# schematic.net
KiCad netlist of a schematic drawn in Altium Designer
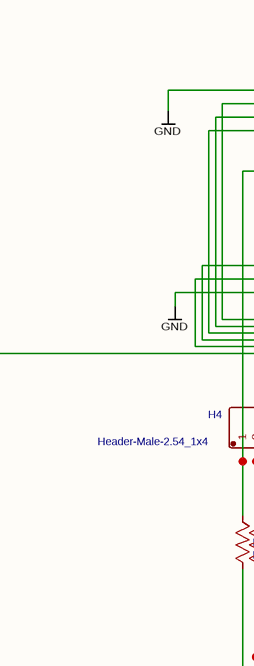
[diagram p0: schematic.schdoc, top left]
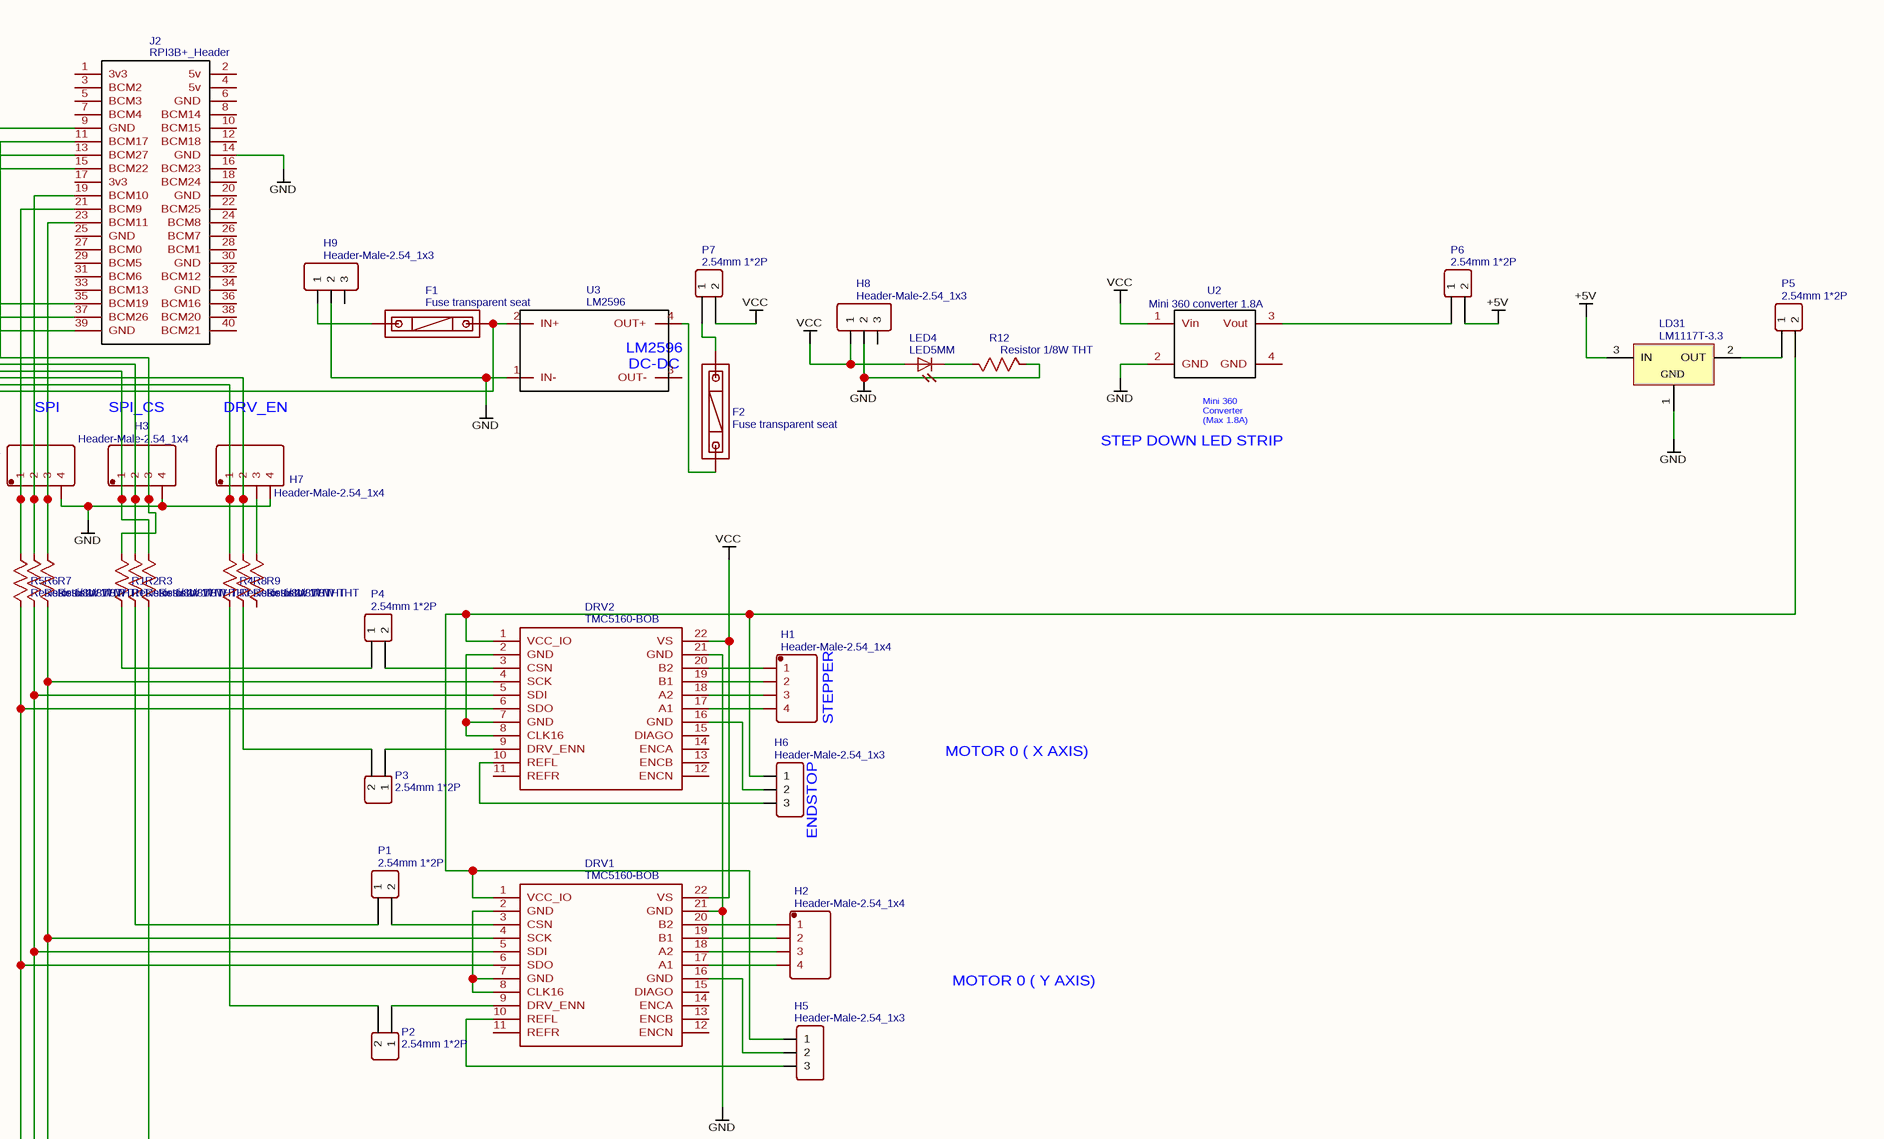
[diagram p1: schematic.schdoc, top right]
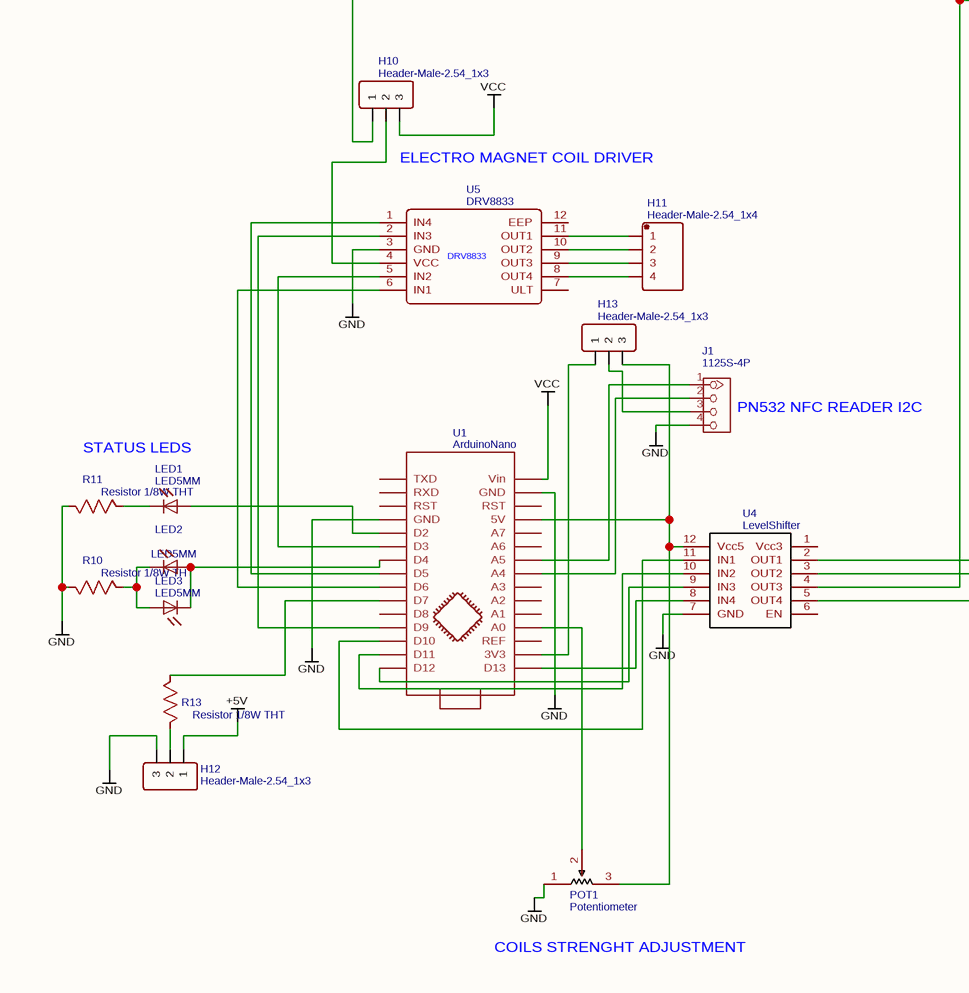
[diagram p2: schematic.schdoc, bottom left]

(export (version "E")
  (design (tool "Eeschema 10.0.6"))
  (components
    (comp (ref "DRV1")
      (value "TMC5160-BOB")
      (fields (field (name "CONTRIBUTOR") "alexackerman96"))
      (libsource (lib "altium-import") (part "root_0_TMC5160-BOB_"))
    )
    (comp (ref "DRV2")
      (value "TMC5160-BOB")
      (fields (field (name "CONTRIBUTOR") "alexackerman96"))
      (libsource (lib "altium-import") (part "root_0_TMC5160-BOB_"))
    )
    (comp (ref "F1")
      (value "Fuse transparent seat")
      (fields (field (name "BOM_SUPPLIER PART") "C58066"))
      (libsource (lib "altium-import") (part "root_0_Fuse transparent seat_"))
    )
    (comp (ref "F2")
      (value "Fuse transparent seat")
      (fields (field (name "BOM_SUPPLIER PART") "C58066"))
      (libsource (lib "altium-import") (part "root_1_Fuse transparent seat_"))
    )
    (comp (ref "H1")
      (value "Header-Male-2.54_1x4")
      (fields
        (field (name "BOM_MANUFACTURER PART") "210S-1*4P L=11.6MMGold-plated black")
        (field (name "BOM_SUPPLIER PART") "C124378")
        (field (name "CONTRIBUTOR") "LCSC")
      )
      (libsource (lib "altium-import") (part "root_0_Header-Male-2.54_1x4_"))
    )
    (comp (ref "H2")
      (value "Header-Male-2.54_1x4")
      (fields
        (field (name "BOM_MANUFACTURER PART") "210S-1*4P L=11.6MMGold-plated black")
        (field (name "BOM_SUPPLIER PART") "C124378")
        (field (name "CONTRIBUTOR") "LCSC")
      )
      (libsource (lib "altium-import") (part "root_0_Header-Male-2.54_1x4_"))
    )
    (comp (ref "H3")
      (value "Header-Male-2.54_1x4")
      (fields
        (field (name "BOM_MANUFACTURER PART") "210S-1*4P L=11.6MMGold-plated black")
        (field (name "BOM_SUPPLIER PART") "C124378")
        (field (name "CONTRIBUTOR") "LCSC")
      )
      (libsource (lib "altium-import") (part "root_1_Header-Male-2.54_1x4_"))
    )
    (comp (ref "H4")
      (value "Header-Male-2.54_1x4")
      (fields
        (field (name "BOM_MANUFACTURER PART") "210S-1*4P L=11.6MMGold-plated black")
        (field (name "BOM_SUPPLIER PART") "C124378")
        (field (name "CONTRIBUTOR") "LCSC")
      )
      (libsource (lib "altium-import") (part "root_1_Header-Male-2.54_1x4_"))
    )
    (comp (ref "H5")
      (value "Header-Male-2.54_1x3")
      (fields
        (field (name "BOM_MANUFACTURER PART") "Header2.54mm 1*3P")
        (field (name "BOM_SUPPLIER PART") "C49257")
      )
      (libsource (lib "altium-import") (part "root_0_Header-Male-2.54_1x3_"))
    )
    (comp (ref "H6")
      (value "Header-Male-2.54_1x3")
      (fields
        (field (name "BOM_MANUFACTURER PART") "Header2.54mm 1*3P")
        (field (name "BOM_SUPPLIER PART") "C49257")
      )
      (libsource (lib "altium-import") (part "root_0_Header-Male-2.54_1x3_"))
    )
    (comp (ref "H7")
      (value "Header-Male-2.54_1x4")
      (fields
        (field (name "BOM_MANUFACTURER PART") "210S-1*4P L=11.6MMGold-plated black")
        (field (name "BOM_SUPPLIER PART") "C124378")
        (field (name "CONTRIBUTOR") "LCSC")
      )
      (libsource (lib "altium-import") (part "root_1_Header-Male-2.54_1x4_"))
    )
    (comp (ref "H8")
      (value "Header-Male-2.54_1x3")
      (fields
        (field (name "BOM_MANUFACTURER PART") "Header2.54mm 1*3P")
        (field (name "BOM_SUPPLIER PART") "C49257")
      )
      (libsource (lib "altium-import") (part "root_1_Header-Male-2.54_1x3_"))
    )
    (comp (ref "H9")
      (value "Header-Male-2.54_1x3")
      (fields
        (field (name "BOM_MANUFACTURER PART") "Header2.54mm 1*3P")
        (field (name "BOM_SUPPLIER PART") "C49257")
      )
      (libsource (lib "altium-import") (part "root_1_Header-Male-2.54_1x3_"))
    )
    (comp (ref "H10")
      (value "Header-Male-2.54_1x3")
      (fields
        (field (name "BOM_MANUFACTURER PART") "Header2.54mm 1*3P")
        (field (name "BOM_SUPPLIER PART") "C49257")
      )
      (libsource (lib "altium-import") (part "root_1_Header-Male-2.54_1x3_"))
    )
    (comp (ref "H11")
      (value "Header-Male-2.54_1x4")
      (fields
        (field (name "BOM_MANUFACTURER PART") "210S-1*4P L=11.6MMGold-plated black")
        (field (name "BOM_SUPPLIER PART") "C124378")
        (field (name "CONTRIBUTOR") "LCSC")
      )
      (libsource (lib "altium-import") (part "root_0_Header-Male-2.54_1x4_"))
    )
    (comp (ref "H12")
      (value "Header-Male-2.54_1x3")
      (fields
        (field (name "BOM_MANUFACTURER PART") "Header2.54mm 1*3P")
        (field (name "BOM_SUPPLIER PART") "C49257")
      )
      (libsource (lib "altium-import") (part "root_3_Header-Male-2.54_1x3_"))
    )
    (comp (ref "H13")
      (value "Header-Male-2.54_1x3")
      (fields
        (field (name "BOM_MANUFACTURER PART") "Header2.54mm 1*3P")
        (field (name "BOM_SUPPLIER PART") "C49257")
      )
      (libsource (lib "altium-import") (part "root_1_Header-Male-2.54_1x3_"))
    )
    (comp (ref "J1")
      (value "1125S-4P")
      (description "DIP Grove")
      (libsource (lib "altium-import") (part "root_0_1125S-4P_"))
    )
    (comp (ref "J2")
      (value "RPI3B+_Header")
      (fields
        (field (name "BOM_MANUFACTURER PART") "61304021121")
        (field (name "BOM_SUPPLIER PART") "732-5310-ND")
        (field (name "CONTRIBUTOR") "boulou")
      )
      (libsource (lib "altium-import") (part "root_0_RPI3B+_Header_"))
    )
    (comp (ref "LD31")
      (value "LM1117T-3.3")
      (fields (field (name "CONTRIBUTOR") "M474"))
      (libsource (lib "altium-import") (part "root_0_LM1117T-3.3_"))
    )
    (comp (ref "LED1")
      (value "LED5MM")
      (description "LEDs")
      (fields (field (name "CONTRIBUTOR") "Pinoccio"))
      (libsource (lib "altium-import") (part "root_3_LED5MM_"))
    )
    (comp (ref "LED2")
      (value "LED5MM")
      (description "LEDs")
      (fields (field (name "CONTRIBUTOR") "Pinoccio"))
      (libsource (lib "altium-import") (part "root_3_LED5MM_"))
    )
    (comp (ref "LED3")
      (value "LED5MM")
      (description "LEDs")
      (fields (field (name "CONTRIBUTOR") "Pinoccio"))
      (libsource (lib "altium-import") (part "root_1_LED5MM_"))
    )
    (comp (ref "LED4")
      (value "LED5MM")
      (description "LEDs")
      (fields (field (name "CONTRIBUTOR") "Pinoccio"))
      (libsource (lib "altium-import") (part "root_1_LED5MM_"))
    )
    (comp (ref "P1")
      (value "2.54mm 1*2P")
      (fields (field (name "BOM_SUPPLIER PART") "C36717"))
      (libsource (lib "altium-import") (part "root_1_2.54mm 1*2P_"))
    )
    (comp (ref "P2")
      (value "2.54mm 1*2P")
      (fields (field (name "BOM_SUPPLIER PART") "C36717"))
      (libsource (lib "altium-import") (part "root_3_2.54mm 1*2P_"))
    )
    (comp (ref "P3")
      (value "2.54mm 1*2P")
      (fields (field (name "BOM_SUPPLIER PART") "C36717"))
      (libsource (lib "altium-import") (part "root_3_2.54mm 1*2P_"))
    )
    (comp (ref "P4")
      (value "2.54mm 1*2P")
      (fields (field (name "BOM_SUPPLIER PART") "C36717"))
      (libsource (lib "altium-import") (part "root_1_2.54mm 1*2P_"))
    )
    (comp (ref "P5")
      (value "2.54mm 1*2P")
      (fields (field (name "BOM_SUPPLIER PART") "C36717"))
      (libsource (lib "altium-import") (part "root_1_2.54mm 1*2P_"))
    )
    (comp (ref "P6")
      (value "2.54mm 1*2P")
      (fields (field (name "BOM_SUPPLIER PART") "C36717"))
      (libsource (lib "altium-import") (part "root_1_2.54mm 1*2P_"))
    )
    (comp (ref "P7")
      (value "2.54mm 1*2P")
      (fields (field (name "BOM_SUPPLIER PART") "C36717"))
      (libsource (lib "altium-import") (part "root_1_2.54mm 1*2P_"))
    )
    (comp (ref "POT1")
      (value "Potentiometer")
      (fields
        (field (name "BOM_MANUFACTURER PART") "potentiometer")
        (field (name "CONTRIBUTOR") "Tommaso Mariotti")
      )
      (libsource (lib "altium-import") (part "root_0_Potentiometer_"))
    )
    (comp (ref "R1")
      (value "Resistor 1/8W THT")
      (fields (field (name "BOM_MANUFACTURER PART") "Generic") (field (name "CONTRIBUTOR") "tyvogelpohl"))
      (libsource (lib "altium-import") (part "root_1_Resistor 1/8W THT_"))
    )
    (comp (ref "R2")
      (value "Resistor 1/8W THT")
      (fields (field (name "BOM_MANUFACTURER PART") "Generic") (field (name "CONTRIBUTOR") "tyvogelpohl"))
      (libsource (lib "altium-import") (part "root_1_Resistor 1/8W THT_"))
    )
    (comp (ref "R3")
      (value "Resistor 1/8W THT")
      (fields (field (name "BOM_MANUFACTURER PART") "Generic") (field (name "CONTRIBUTOR") "tyvogelpohl"))
      (libsource (lib "altium-import") (part "root_1_Resistor 1/8W THT_"))
    )
    (comp (ref "R4")
      (value "Resistor 1/8W THT")
      (fields (field (name "BOM_MANUFACTURER PART") "Generic") (field (name "CONTRIBUTOR") "tyvogelpohl"))
      (libsource (lib "altium-import") (part "root_1_Resistor 1/8W THT_"))
    )
    (comp (ref "R5")
      (value "Resistor 1/8W THT")
      (fields (field (name "BOM_MANUFACTURER PART") "Generic") (field (name "CONTRIBUTOR") "tyvogelpohl"))
      (libsource (lib "altium-import") (part "root_1_Resistor 1/8W THT_"))
    )
    (comp (ref "R6")
      (value "Resistor 1/8W THT")
      (fields (field (name "BOM_MANUFACTURER PART") "Generic") (field (name "CONTRIBUTOR") "tyvogelpohl"))
      (libsource (lib "altium-import") (part "root_1_Resistor 1/8W THT_"))
    )
    (comp (ref "R7")
      (value "Resistor 1/8W THT")
      (fields (field (name "BOM_MANUFACTURER PART") "Generic") (field (name "CONTRIBUTOR") "tyvogelpohl"))
      (libsource (lib "altium-import") (part "root_1_Resistor 1/8W THT_"))
    )
    (comp (ref "R8")
      (value "Resistor 1/8W THT")
      (fields (field (name "BOM_MANUFACTURER PART") "Generic") (field (name "CONTRIBUTOR") "tyvogelpohl"))
      (libsource (lib "altium-import") (part "root_1_Resistor 1/8W THT_"))
    )
    (comp (ref "R9")
      (value "Resistor 1/8W THT")
      (fields (field (name "BOM_MANUFACTURER PART") "Generic") (field (name "CONTRIBUTOR") "tyvogelpohl"))
      (libsource (lib "altium-import") (part "root_1_Resistor 1/8W THT_"))
    )
    (comp (ref "R10")
      (value "Resistor 1/8W THT")
      (fields (field (name "BOM_MANUFACTURER PART") "Generic") (field (name "CONTRIBUTOR") "tyvogelpohl"))
      (libsource (lib "altium-import") (part "root_2_Resistor 1/8W THT_"))
    )
    (comp (ref "R11")
      (value "Resistor 1/8W THT")
      (fields (field (name "BOM_MANUFACTURER PART") "Generic") (field (name "CONTRIBUTOR") "tyvogelpohl"))
      (libsource (lib "altium-import") (part "root_2_Resistor 1/8W THT_"))
    )
    (comp (ref "R12")
      (value "Resistor 1/8W THT")
      (fields (field (name "BOM_MANUFACTURER PART") "Generic") (field (name "CONTRIBUTOR") "tyvogelpohl"))
      (libsource (lib "altium-import") (part "root_0_Resistor 1/8W THT_"))
    )
    (comp (ref "R13")
      (value "Resistor 1/8W THT")
      (fields (field (name "BOM_MANUFACTURER PART") "Generic") (field (name "CONTRIBUTOR") "tyvogelpohl"))
      (libsource (lib "altium-import") (part "root_3_Resistor 1/8W THT_"))
    )
    (comp (ref "U1")
      (value "ArduinoNano")
      (fields (field (name "CONTRIBUTOR") "vincint810923"))
      (libsource (lib "altium-import") (part "root_0_ArduinoNano_"))
    )
    (comp (ref "U2")
      (value "Mini 360 converter 1.8A")
      (fields
        (field (name "BOM_MANUFACTURER PART") "Mini 360 step down converter 1.8A")
        (field (name "CONTRIBUTOR") "Hankwon Chang (InterStellarCloud)")
      )
      (libsource (lib "altium-import") (part "root_0_Mini 360 converter 1.8A_"))
    )
    (comp (ref "U3")
      (value "LM2596")
      (fields (field (name "CONTRIBUTOR") "Azriel Hutagalung"))
      (libsource (lib "altium-import") (part "root_0_LM2596_"))
    )
    (comp (ref "U4")
      (value "LevelShifter")
      (fields (field (name "CONTRIBUTOR") "max.helmrich"))
      (libsource (lib "altium-import") (part "root_0_LevelShifter_"))
    )
    (comp (ref "U5") (value "DRV8833") (libsource (lib "altium-import") (part "root_0_DRV8833_")))
  )
  (nets
    (net (code "1") (name "+5V") (class "Default")
      (node (ref "H12") (pin "1") (pinfunction "1_1") (pintype "passive"))
      (node (ref "LD31") (pin "3") (pinfunction "IN_3") (pintype "passive"))
      (node (ref "P6") (pin "2") (pinfunction "2_2") (pintype "passive"))
    )
    (net (code "2") (name "GND") (class "Default")
      (node (ref "DRV1") (pin "21") (pinfunction "GND_21") (pintype "passive"))
      (node (ref "DRV2") (pin "21") (pinfunction "GND_21") (pintype "passive"))
      (node (ref "H12") (pin "3") (pinfunction "3_3") (pintype "passive"))
      (node (ref "H3") (pin "4") (pinfunction "4_4") (pintype "passive"))
      (node (ref "H4") (pin "4") (pinfunction "4_4") (pintype "passive"))
      (node (ref "H7") (pin "4") (pinfunction "4_4") (pintype "passive"))
      (node (ref "H8") (pin "2") (pinfunction "2_2") (pintype "passive"))
      (node (ref "H9") (pin "2") (pinfunction "2_2") (pintype "passive"))
      (node (ref "J1") (pin "4") (pinfunction "4_4") (pintype "passive"))
      (node (ref "J2") (pin "14") (pinfunction "GND_14") (pintype "passive"))
      (node (ref "J2") (pin "39") (pinfunction "GND_39") (pintype "passive"))
      (node (ref "J2") (pin "9") (pinfunction "GND_9") (pintype "passive"))
      (node (ref "LD31") (pin "1") (pinfunction "GND_1") (pintype "passive"))
      (node (ref "POT1") (pin "1") (pinfunction "1_1") (pintype "passive"))
      (node (ref "R10") (pin "2") (pinfunction "2_2") (pintype "passive"))
      (node (ref "R11") (pin "2") (pinfunction "2_2") (pintype "passive"))
      (node (ref "R12") (pin "2") (pinfunction "2_2") (pintype "passive"))
      (node (ref "U1") (pin "29") (pinfunction "GND_29") (pintype "passive"))
      (node (ref "U1") (pin "4") (pinfunction "GND_4") (pintype "passive"))
      (node (ref "U2") (pin "2") (pinfunction "GND_2") (pintype "passive"))
      (node (ref "U3") (pin "1") (pinfunction "IN-_1") (pintype "passive"))
      (node (ref "U4") (pin "7") (pinfunction "GND_7") (pintype "passive"))
      (node (ref "U5") (pin "3") (pinfunction "GND_3") (pintype "passive"))
    )
    (net (code "3") (name "Net-(DRV1-A1)") (class "Default")
      (node (ref "DRV1") (pin "17") (pinfunction "A1_17") (pintype "passive"))
      (node (ref "H2") (pin "4") (pinfunction "4_4") (pintype "passive"))
    )
    (net (code "4") (name "Net-(DRV1-A2)") (class "Default")
      (node (ref "DRV1") (pin "18") (pinfunction "A2_18") (pintype "passive"))
      (node (ref "H2") (pin "3") (pinfunction "3_3") (pintype "passive"))
    )
    (net (code "5") (name "Net-(DRV1-B1)") (class "Default")
      (node (ref "DRV1") (pin "19") (pinfunction "B1_19") (pintype "passive"))
      (node (ref "H2") (pin "2") (pinfunction "2_2") (pintype "passive"))
    )
    (net (code "6") (name "Net-(DRV1-B2)") (class "Default")
      (node (ref "DRV1") (pin "20") (pinfunction "B2_20") (pintype "passive"))
      (node (ref "H2") (pin "1") (pinfunction "1_1") (pintype "passive"))
    )
    (net (code "7") (name "Net-(DRV1-CLK16)") (class "Default")
      (node (ref "DRV1") (pin "2") (pinfunction "GND_2") (pintype "passive"))
      (node (ref "DRV1") (pin "7") (pinfunction "GND_7") (pintype "passive"))
      (node (ref "DRV1") (pin "8") (pinfunction "CLK16_8") (pintype "passive"))
    )
    (net (code "8") (name "Net-(DRV1-CSN)") (class "Default")
      (node (ref "DRV1") (pin "3") (pinfunction "CSN_3") (pintype "passive"))
      (node (ref "P1") (pin "2") (pinfunction "2_2") (pintype "passive"))
    )
    (net (code "9") (name "Net-(DRV1-DRV_ENN)") (class "Default")
      (node (ref "DRV1") (pin "9") (pinfunction "DRV_ENN_9") (pintype "passive"))
      (node (ref "P2") (pin "1") (pinfunction "1_1") (pintype "passive"))
    )
    (net (code "10") (name "Net-(DRV1-GND-Pad16)") (class "Default")
      (node (ref "DRV1") (pin "16") (pinfunction "GND_16") (pintype "passive"))
      (node (ref "H5") (pin "2") (pinfunction "2_2") (pintype "passive"))
    )
    (net (code "11") (name "Net-(DRV1-REFL)") (class "Default")
      (node (ref "DRV1") (pin "10") (pinfunction "REFL_10") (pintype "passive"))
      (node (ref "H5") (pin "3") (pinfunction "3_3") (pintype "passive"))
    )
    (net (code "12") (name "Net-(DRV1-SCK)") (class "Default")
      (node (ref "DRV1") (pin "4") (pinfunction "SCK_4") (pintype "passive"))
      (node (ref "DRV2") (pin "4") (pinfunction "SCK_4") (pintype "passive"))
      (node (ref "R7") (pin "1") (pinfunction "1_1") (pintype "passive"))
      (node (ref "U4") (pin "5") (pinfunction "OUT4_5") (pintype "passive"))
    )
    (net (code "13") (name "Net-(DRV1-SDI)") (class "Default")
      (node (ref "DRV1") (pin "5") (pinfunction "SDI_5") (pintype "passive"))
      (node (ref "DRV2") (pin "5") (pinfunction "SDI_5") (pintype "passive"))
      (node (ref "R6") (pin "1") (pinfunction "1_1") (pintype "passive"))
      (node (ref "U4") (pin "3") (pinfunction "OUT2_3") (pintype "passive"))
    )
    (net (code "14") (name "Net-(DRV1-SDO)") (class "Default")
      (node (ref "DRV1") (pin "6") (pinfunction "SDO_6") (pintype "passive"))
      (node (ref "DRV2") (pin "6") (pinfunction "SDO_6") (pintype "passive"))
      (node (ref "R5") (pin "1") (pinfunction "1_1") (pintype "passive"))
      (node (ref "U4") (pin "4") (pinfunction "OUT3_4") (pintype "passive"))
    )
    (net (code "15") (name "Net-(DRV1-VCC_IO)") (class "Default")
      (node (ref "DRV1") (pin "1") (pinfunction "VCC_IO_1") (pintype "passive"))
      (node (ref "DRV2") (pin "1") (pinfunction "VCC_IO_1") (pintype "passive"))
      (node (ref "H5") (pin "1") (pinfunction "1_1") (pintype "passive"))
      (node (ref "H6") (pin "1") (pinfunction "1_1") (pintype "passive"))
      (node (ref "P5") (pin "2") (pinfunction "2_2") (pintype "passive"))
    )
    (net (code "16") (name "Net-(DRV2-A1)") (class "Default")
      (node (ref "DRV2") (pin "17") (pinfunction "A1_17") (pintype "passive"))
      (node (ref "H1") (pin "4") (pinfunction "4_4") (pintype "passive"))
    )
    (net (code "17") (name "Net-(DRV2-A2)") (class "Default")
      (node (ref "DRV2") (pin "18") (pinfunction "A2_18") (pintype "passive"))
      (node (ref "H1") (pin "3") (pinfunction "3_3") (pintype "passive"))
    )
    (net (code "18") (name "Net-(DRV2-B1)") (class "Default")
      (node (ref "DRV2") (pin "19") (pinfunction "B1_19") (pintype "passive"))
      (node (ref "H1") (pin "2") (pinfunction "2_2") (pintype "passive"))
    )
    (net (code "19") (name "Net-(DRV2-B2)") (class "Default")
      (node (ref "DRV2") (pin "20") (pinfunction "B2_20") (pintype "passive"))
      (node (ref "H1") (pin "1") (pinfunction "1_1") (pintype "passive"))
    )
    (net (code "20") (name "Net-(DRV2-CLK16)") (class "Default")
      (node (ref "DRV2") (pin "2") (pinfunction "GND_2") (pintype "passive"))
      (node (ref "DRV2") (pin "7") (pinfunction "GND_7") (pintype "passive"))
      (node (ref "DRV2") (pin "8") (pinfunction "CLK16_8") (pintype "passive"))
    )
    (net (code "21") (name "Net-(DRV2-CSN)") (class "Default")
      (node (ref "DRV2") (pin "3") (pinfunction "CSN_3") (pintype "passive"))
      (node (ref "P4") (pin "2") (pinfunction "2_2") (pintype "passive"))
    )
    (net (code "22") (name "Net-(DRV2-DRV_ENN)") (class "Default")
      (node (ref "DRV2") (pin "9") (pinfunction "DRV_ENN_9") (pintype "passive"))
      (node (ref "P3") (pin "1") (pinfunction "1_1") (pintype "passive"))
    )
    (net (code "23") (name "Net-(DRV2-GND-Pad16)") (class "Default")
      (node (ref "DRV2") (pin "16") (pinfunction "GND_16") (pintype "passive"))
      (node (ref "H6") (pin "2") (pinfunction "2_2") (pintype "passive"))
    )
    (net (code "24") (name "Net-(DRV2-REFL)") (class "Default")
      (node (ref "DRV2") (pin "10") (pinfunction "REFL_10") (pintype "passive"))
      (node (ref "H6") (pin "3") (pinfunction "3_3") (pintype "passive"))
    )
    (net (code "25") (name "Net-(F1-Pad1)") (class "Default")
      (node (ref "F1") (pin "1") (pinfunction "1_1") (pintype "passive"))
      (node (ref "H9") (pin "1") (pinfunction "1_1") (pintype "passive"))
    )
    (net (code "26") (name "Net-(F2-Pad2)") (class "Default")
      (node (ref "F2") (pin "2") (pinfunction "2_2") (pintype "passive"))
      (node (ref "P7") (pin "1") (pinfunction "1_1") (pintype "passive"))
    )
    (net (code "27") (name "Net-(H7-Pad3)") (class "Default")
      (node (ref "H7") (pin "3") (pinfunction "3_3") (pintype "passive"))
      (node (ref "R9") (pin "2") (pinfunction "2_2") (pintype "passive"))
    )
    (net (code "28") (name "Net-(H12-Pad2)") (class "Default")
      (node (ref "H12") (pin "2") (pinfunction "2_2") (pintype "passive"))
      (node (ref "R13") (pin "2") (pinfunction "2_2") (pintype "passive"))
    )
    (net (code "29") (name "Net-(H13-Pad2)") (class "Default")
      (node (ref "H13") (pin "2") (pinfunction "2_2") (pintype "passive"))
      (node (ref "J1") (pin "3") (pinfunction "3_3") (pintype "passive"))
    )
    (net (code "30") (name "Net-(J2-BCM9)") (class "Default")
      (node (ref "H4") (pin "1") (pinfunction "1_1") (pintype "passive"))
      (node (ref "J2") (pin "21") (pinfunction "BCM9_21") (pintype "passive"))
      (node (ref "R5") (pin "2") (pinfunction "2_2") (pintype "passive"))
    )
    (net (code "31") (name "Net-(J2-BCM10)") (class "Default")
      (node (ref "H4") (pin "2") (pinfunction "2_2") (pintype "passive"))
      (node (ref "J2") (pin "19") (pinfunction "BCM10_19") (pintype "passive"))
      (node (ref "R6") (pin "2") (pinfunction "2_2") (pintype "passive"))
    )
    (net (code "32") (name "Net-(J2-BCM11)") (class "Default")
      (node (ref "H4") (pin "3") (pinfunction "3_3") (pintype "passive"))
      (node (ref "J2") (pin "23") (pinfunction "BCM11_23") (pintype "passive"))
      (node (ref "R7") (pin "2") (pinfunction "2_2") (pintype "passive"))
    )
    (net (code "33") (name "Net-(J2-BCM17)") (class "Default")
      (node (ref "H3") (pin "3") (pinfunction "3_3") (pintype "passive"))
      (node (ref "J2") (pin "11") (pinfunction "BCM17_11") (pintype "passive"))
      (node (ref "R1") (pin "2") (pinfunction "2_2") (pintype "passive"))
    )
    (net (code "34") (name "Net-(J2-BCM19)") (class "Default")
      (node (ref "H7") (pin "2") (pinfunction "2_2") (pintype "passive"))
      (node (ref "J2") (pin "35") (pinfunction "BCM19_35") (pintype "passive"))
      (node (ref "R8") (pin "2") (pinfunction "2_2") (pintype "passive"))
    )
    (net (code "35") (name "Net-(J2-BCM22)") (class "Default")
      (node (ref "H3") (pin "1") (pinfunction "1_1") (pintype "passive"))
      (node (ref "J2") (pin "15") (pinfunction "BCM22_15") (pintype "passive"))
      (node (ref "R3") (pin "2") (pinfunction "2_2") (pintype "passive"))
    )
    (net (code "36") (name "Net-(J2-BCM26)") (class "Default")
      (node (ref "H7") (pin "1") (pinfunction "1_1") (pintype "passive"))
      (node (ref "J2") (pin "37") (pinfunction "BCM26_37") (pintype "passive"))
      (node (ref "R4") (pin "2") (pinfunction "2_2") (pintype "passive"))
    )
    (net (code "37") (name "Net-(J2-BCM27)") (class "Default")
      (node (ref "H3") (pin "2") (pinfunction "2_2") (pintype "passive"))
      (node (ref "J2") (pin "13") (pinfunction "BCM27_13") (pintype "passive"))
      (node (ref "R2") (pin "2") (pinfunction "2_2") (pintype "passive"))
    )
    (net (code "38") (name "Net-(LD31-OUT)") (class "Default")
      (node (ref "LD31") (pin "2") (pinfunction "OUT_2") (pintype "passive"))
      (node (ref "P5") (pin "1") (pinfunction "1_1") (pintype "passive"))
    )
    (net (code "39") (name "Net-(LED1-C)") (class "Default")
      (node (ref "LED1") (pin "K") (pinfunction "C_K") (pintype "passive"))
      (node (ref "R11") (pin "1") (pinfunction "1_1") (pintype "passive"))
    )
    (net (code "40") (name "Net-(LED2-C)") (class "Default")
      (node (ref "LED2") (pin "K") (pinfunction "C_K") (pintype "passive"))
      (node (ref "LED3") (pin "A") (pinfunction "A_A") (pintype "passive"))
      (node (ref "R10") (pin "1") (pinfunction "1_1") (pintype "passive"))
    )
    (net (code "41") (name "Net-(LED3-C)") (class "Default")
      (node (ref "LED2") (pin "A") (pinfunction "A_A") (pintype "passive"))
      (node (ref "LED3") (pin "K") (pinfunction "C_K") (pintype "passive"))
      (node (ref "U1") (pin "7") (pinfunction "D4_7") (pintype "passive"))
    )
    (net (code "42") (name "Net-(LED4-C)") (class "Default")
      (node (ref "LED4") (pin "K") (pinfunction "C_K") (pintype "passive"))
      (node (ref "R12") (pin "1") (pinfunction "1_1") (pintype "passive"))
    )
    (net (code "43") (name "Net-(P1-Pad1)") (class "Default")
      (node (ref "P1") (pin "1") (pinfunction "1_1") (pintype "passive"))
      (node (ref "R2") (pin "1") (pinfunction "1_1") (pintype "passive"))
    )
    (net (code "44") (name "Net-(P2-Pad2)") (class "Default")
      (node (ref "P2") (pin "2") (pinfunction "2_2") (pintype "passive"))
      (node (ref "R4") (pin "1") (pinfunction "1_1") (pintype "passive"))
    )
    (net (code "45") (name "Net-(P3-Pad2)") (class "Default")
      (node (ref "P3") (pin "2") (pinfunction "2_2") (pintype "passive"))
      (node (ref "R8") (pin "1") (pinfunction "1_1") (pintype "passive"))
    )
    (net (code "46") (name "Net-(P4-Pad1)") (class "Default")
      (node (ref "P4") (pin "1") (pinfunction "1_1") (pintype "passive"))
      (node (ref "R1") (pin "1") (pinfunction "1_1") (pintype "passive"))
    )
    (net (code "47") (name "Net-(U1-3V3)") (class "Default")
      (node (ref "H13") (pin "1") (pinfunction "1_1") (pintype "passive"))
      (node (ref "U1") (pin "17") (pinfunction "3V3_17") (pintype "passive"))
    )
    (net (code "48") (name "Net-(U1-5V)") (class "Default")
      (node (ref "H13") (pin "3") (pinfunction "3_3") (pintype "passive"))
      (node (ref "POT1") (pin "3") (pinfunction "3_3") (pintype "passive"))
      (node (ref "U1") (pin "27") (pinfunction "5V_27") (pintype "passive"))
      (node (ref "U4") (pin "12") (pinfunction "Vcc5_12") (pintype "passive"))
    )
    (net (code "49") (name "Net-(U1-A0)") (class "Default")
      (node (ref "POT1") (pin "2") (pinfunction "2_2") (pintype "passive"))
      (node (ref "U1") (pin "19") (pinfunction "A0_19") (pintype "passive"))
    )
    (net (code "50") (name "Net-(U1-A4)") (class "Default")
      (node (ref "J1") (pin "2") (pinfunction "2_2") (pintype "passive"))
      (node (ref "U1") (pin "23") (pinfunction "A4_23") (pintype "passive"))
    )
    (net (code "51") (name "Net-(U1-A5)") (class "Default")
      (node (ref "J1") (pin "1") (pinfunction "1_1") (pintype "passive"))
      (node (ref "U1") (pin "24") (pinfunction "A5_24") (pintype "passive"))
    )
    (net (code "52") (name "Net-(U1-D2)") (class "Default")
      (node (ref "LED1") (pin "A") (pinfunction "A_A") (pintype "passive"))
      (node (ref "U1") (pin "5") (pinfunction "D2_5") (pintype "passive"))
    )
    (net (code "53") (name "Net-(U1-D3)") (class "Default")
      (node (ref "U1") (pin "6") (pinfunction "D3_6") (pintype "passive"))
      (node (ref "U5") (pin "5") (pinfunction "IN2_5") (pintype "passive"))
    )
    (net (code "54") (name "Net-(U1-D5)") (class "Default")
      (node (ref "U1") (pin "8") (pinfunction "D5_8") (pintype "passive"))
      (node (ref "U5") (pin "1") (pinfunction "IN4_1") (pintype "passive"))
    )
    (net (code "55") (name "Net-(U1-D6)") (class "Default")
      (node (ref "U1") (pin "9") (pinfunction "D6_9") (pintype "passive"))
      (node (ref "U5") (pin "6") (pinfunction "IN1_6") (pintype "passive"))
    )
    (net (code "56") (name "Net-(U1-D7)") (class "Default")
      (node (ref "R13") (pin "1") (pinfunction "1_1") (pintype "passive"))
      (node (ref "U1") (pin "10") (pinfunction "D7_10") (pintype "passive"))
    )
    (net (code "57") (name "Net-(U1-D9)") (class "Default")
      (node (ref "U1") (pin "12") (pinfunction "D9_12") (pintype "passive"))
      (node (ref "U5") (pin "2") (pinfunction "IN3_2") (pintype "passive"))
    )
    (net (code "58") (name "Net-(U1-D10)") (class "Default")
      (node (ref "U1") (pin "13") (pinfunction "D10_13") (pintype "passive"))
      (node (ref "U4") (pin "11") (pinfunction "IN1_11") (pintype "passive"))
    )
    (net (code "59") (name "Net-(U1-D11)") (class "Default")
      (node (ref "U1") (pin "14") (pinfunction "D11_14") (pintype "passive"))
      (node (ref "U4") (pin "10") (pinfunction "IN2_10") (pintype "passive"))
    )
    (net (code "60") (name "Net-(U1-D12)") (class "Default")
      (node (ref "U1") (pin "15") (pinfunction "D12_15") (pintype "passive"))
      (node (ref "U4") (pin "9") (pinfunction "IN3_9") (pintype "passive"))
    )
    (net (code "61") (name "Net-(U1-D13)") (class "Default")
      (node (ref "U1") (pin "16") (pinfunction "D13_16") (pintype "passive"))
      (node (ref "U4") (pin "8") (pinfunction "IN4_8") (pintype "passive"))
    )
    (net (code "62") (name "Net-(U2-Vout)") (class "Default")
      (node (ref "P6") (pin "1") (pinfunction "1_1") (pintype "passive"))
      (node (ref "U2") (pin "3") (pinfunction "Vout_3") (pintype "passive"))
    )
    (net (code "63") (name "Net-(U3-IN+)") (class "Default")
      (node (ref "F1") (pin "2") (pinfunction "2_2") (pintype "passive"))
      (node (ref "H10") (pin "1") (pinfunction "1_1") (pintype "passive"))
      (node (ref "U3") (pin "2") (pinfunction "IN+_2") (pintype "passive"))
    )
    (net (code "64") (name "Net-(U3-OUT+)") (class "Default")
      (node (ref "F2") (pin "1") (pinfunction "1_1") (pintype "passive"))
      (node (ref "U3") (pin "4") (pinfunction "OUT+_4") (pintype "passive"))
    )
    (net (code "65") (name "Net-(U4-OUT1)") (class "Default")
      (node (ref "R3") (pin "1") (pinfunction "1_1") (pintype "passive"))
      (node (ref "U4") (pin "2") (pinfunction "OUT1_2") (pintype "passive"))
    )
    (net (code "66") (name "Net-(U5-OUT1)") (class "Default")
      (node (ref "H11") (pin "1") (pinfunction "1_1") (pintype "passive"))
      (node (ref "U5") (pin "11") (pinfunction "OUT1_11") (pintype "passive"))
    )
    (net (code "67") (name "Net-(U5-OUT2)") (class "Default")
      (node (ref "H11") (pin "2") (pinfunction "2_2") (pintype "passive"))
      (node (ref "U5") (pin "10") (pinfunction "OUT2_10") (pintype "passive"))
    )
    (net (code "68") (name "Net-(U5-OUT3)") (class "Default")
      (node (ref "H11") (pin "3") (pinfunction "3_3") (pintype "passive"))
      (node (ref "U5") (pin "9") (pinfunction "OUT3_9") (pintype "passive"))
    )
    (net (code "69") (name "Net-(U5-OUT4)") (class "Default")
      (node (ref "H11") (pin "4") (pinfunction "4_4") (pintype "passive"))
      (node (ref "U5") (pin "8") (pinfunction "OUT4_8") (pintype "passive"))
    )
    (net (code "70") (name "Net-(U5-VCC)") (class "Default")
      (node (ref "H10") (pin "2") (pinfunction "2_2") (pintype "passive"))
      (node (ref "U5") (pin "4") (pinfunction "VCC_4") (pintype "passive"))
    )
    (net (code "71") (name "VCC") (class "Default")
      (node (ref "DRV1") (pin "22") (pinfunction "VS_22") (pintype "passive"))
      (node (ref "DRV2") (pin "22") (pinfunction "VS_22") (pintype "passive"))
      (node (ref "H10") (pin "3") (pinfunction "3_3") (pintype "passive"))
      (node (ref "H8") (pin "1") (pinfunction "1_1") (pintype "passive"))
      (node (ref "LED4") (pin "A") (pinfunction "A_A") (pintype "passive"))
      (node (ref "P7") (pin "2") (pinfunction "2_2") (pintype "passive"))
      (node (ref "U1") (pin "30") (pinfunction "Vin_30") (pintype "passive"))
      (node (ref "U2") (pin "1") (pinfunction "Vin_1") (pintype "passive"))
    )
    (net (code "72") (name "unconnected-(DRV1-DIAGO-Pad15)") (class "Default")
      (node (ref "DRV1") (pin "15") (pinfunction "DIAGO_15") (pintype "passive"))
    )
    (net (code "73") (name "unconnected-(DRV1-ENCA-Pad14)") (class "Default")
      (node (ref "DRV1") (pin "14") (pinfunction "ENCA_14") (pintype "passive"))
    )
    (net (code "74") (name "unconnected-(DRV1-ENCB-Pad13)") (class "Default")
      (node (ref "DRV1") (pin "13") (pinfunction "ENCB_13") (pintype "passive"))
    )
    (net (code "75") (name "unconnected-(DRV1-ENCN-Pad12)") (class "Default")
      (node (ref "DRV1") (pin "12") (pinfunction "ENCN_12") (pintype "passive"))
    )
    (net (code "76") (name "unconnected-(DRV1-REFR-Pad11)") (class "Default")
      (node (ref "DRV1") (pin "11") (pinfunction "REFR_11") (pintype "passive"))
    )
    (net (code "77") (name "unconnected-(DRV2-DIAGO-Pad15)") (class "Default")
      (node (ref "DRV2") (pin "15") (pinfunction "DIAGO_15") (pintype "passive"))
    )
    (net (code "78") (name "unconnected-(DRV2-ENCA-Pad14)") (class "Default")
      (node (ref "DRV2") (pin "14") (pinfunction "ENCA_14") (pintype "passive"))
    )
    (net (code "79") (name "unconnected-(DRV2-ENCB-Pad13)") (class "Default")
      (node (ref "DRV2") (pin "13") (pinfunction "ENCB_13") (pintype "passive"))
    )
    (net (code "80") (name "unconnected-(DRV2-ENCN-Pad12)") (class "Default")
      (node (ref "DRV2") (pin "12") (pinfunction "ENCN_12") (pintype "passive"))
    )
    (net (code "81") (name "unconnected-(DRV2-REFR-Pad11)") (class "Default")
      (node (ref "DRV2") (pin "11") (pinfunction "REFR_11") (pintype "passive"))
    )
    (net (code "82") (name "unconnected-(H8-Pad3)") (class "Default")
      (node (ref "H8") (pin "3") (pinfunction "3_3") (pintype "passive"))
    )
    (net (code "83") (name "unconnected-(H9-Pad3)") (class "Default")
      (node (ref "H9") (pin "3") (pinfunction "3_3") (pintype "passive"))
    )
    (net (code "84") (name "unconnected-(J2-3v3-Pad1)") (class "Default")
      (node (ref "J2") (pin "1") (pinfunction "3v3_1") (pintype "passive"))
    )
    (net (code "85") (name "unconnected-(J2-3v3-Pad17)") (class "Default")
      (node (ref "J2") (pin "17") (pinfunction "3v3_17") (pintype "passive"))
    )
    (net (code "86") (name "unconnected-(J2-5v-Pad2)") (class "Default")
      (node (ref "J2") (pin "2") (pinfunction "5v_2") (pintype "passive"))
    )
    (net (code "87") (name "unconnected-(J2-5v-Pad4)") (class "Default")
      (node (ref "J2") (pin "4") (pinfunction "5v_4") (pintype "passive"))
    )
    (net (code "88") (name "unconnected-(J2-BCM0-Pad27)") (class "Default")
      (node (ref "J2") (pin "27") (pinfunction "BCM0_27") (pintype "passive"))
    )
    (net (code "89") (name "unconnected-(J2-BCM1-Pad28)") (class "Default")
      (node (ref "J2") (pin "28") (pinfunction "BCM1_28") (pintype "passive"))
    )
    (net (code "90") (name "unconnected-(J2-BCM2-Pad3)") (class "Default")
      (node (ref "J2") (pin "3") (pinfunction "BCM2_3") (pintype "passive"))
    )
    (net (code "91") (name "unconnected-(J2-BCM3-Pad5)") (class "Default")
      (node (ref "J2") (pin "5") (pinfunction "BCM3_5") (pintype "passive"))
    )
    (net (code "92") (name "unconnected-(J2-BCM4-Pad7)") (class "Default")
      (node (ref "J2") (pin "7") (pinfunction "BCM4_7") (pintype "passive"))
    )
    (net (code "93") (name "unconnected-(J2-BCM5-Pad29)") (class "Default")
      (node (ref "J2") (pin "29") (pinfunction "BCM5_29") (pintype "passive"))
    )
    (net (code "94") (name "unconnected-(J2-BCM6-Pad31)") (class "Default")
      (node (ref "J2") (pin "31") (pinfunction "BCM6_31") (pintype "passive"))
    )
    (net (code "95") (name "unconnected-(J2-BCM7-Pad26)") (class "Default")
      (node (ref "J2") (pin "26") (pinfunction "BCM7_26") (pintype "passive"))
    )
    (net (code "96") (name "unconnected-(J2-BCM8-Pad24)") (class "Default")
      (node (ref "J2") (pin "24") (pinfunction "BCM8_24") (pintype "passive"))
    )
    (net (code "97") (name "unconnected-(J2-BCM12-Pad32)") (class "Default")
      (node (ref "J2") (pin "32") (pinfunction "BCM12_32") (pintype "passive"))
    )
    (net (code "98") (name "unconnected-(J2-BCM13-Pad33)") (class "Default")
      (node (ref "J2") (pin "33") (pinfunction "BCM13_33") (pintype "passive"))
    )
    (net (code "99") (name "unconnected-(J2-BCM14-Pad8)") (class "Default")
      (node (ref "J2") (pin "8") (pinfunction "BCM14_8") (pintype "passive"))
    )
    (net (code "100") (name "unconnected-(J2-BCM15-Pad10)") (class "Default")
      (node (ref "J2") (pin "10") (pinfunction "BCM15_10") (pintype "passive"))
    )
    (net (code "101") (name "unconnected-(J2-BCM16-Pad36)") (class "Default")
      (node (ref "J2") (pin "36") (pinfunction "BCM16_36") (pintype "passive"))
    )
    (net (code "102") (name "unconnected-(J2-BCM18-Pad12)") (class "Default")
      (node (ref "J2") (pin "12") (pinfunction "BCM18_12") (pintype "passive"))
    )
    (net (code "103") (name "unconnected-(J2-BCM20-Pad38)") (class "Default")
      (node (ref "J2") (pin "38") (pinfunction "BCM20_38") (pintype "passive"))
    )
    (net (code "104") (name "unconnected-(J2-BCM21-Pad40)") (class "Default")
      (node (ref "J2") (pin "40") (pinfunction "BCM21_40") (pintype "passive"))
    )
    (net (code "105") (name "unconnected-(J2-BCM23-Pad16)") (class "Default")
      (node (ref "J2") (pin "16") (pinfunction "BCM23_16") (pintype "passive"))
    )
    (net (code "106") (name "unconnected-(J2-BCM24-Pad18)") (class "Default")
      (node (ref "J2") (pin "18") (pinfunction "BCM24_18") (pintype "passive"))
    )
    (net (code "107") (name "unconnected-(J2-BCM25-Pad22)") (class "Default")
      (node (ref "J2") (pin "22") (pinfunction "BCM25_22") (pintype "passive"))
    )
    (net (code "108") (name "unconnected-(J2-GND-Pad6)") (class "Default")
      (node (ref "J2") (pin "6") (pinfunction "GND_6") (pintype "passive"))
    )
    (net (code "109") (name "unconnected-(J2-GND-Pad20)") (class "Default")
      (node (ref "J2") (pin "20") (pinfunction "GND_20") (pintype "passive"))
    )
    (net (code "110") (name "unconnected-(J2-GND-Pad25)") (class "Default")
      (node (ref "J2") (pin "25") (pinfunction "GND_25") (pintype "passive"))
    )
    (net (code "111") (name "unconnected-(J2-GND-Pad30)") (class "Default")
      (node (ref "J2") (pin "30") (pinfunction "GND_30") (pintype "passive"))
    )
    (net (code "112") (name "unconnected-(J2-GND-Pad34)") (class "Default")
      (node (ref "J2") (pin "34") (pinfunction "GND_34") (pintype "passive"))
    )
    (net (code "113") (name "unconnected-(R9-Pad1)") (class "Default")
      (node (ref "R9") (pin "1") (pinfunction "1_1") (pintype "passive"))
    )
    (net (code "114") (name "unconnected-(U1-A1-Pad20)") (class "Default")
      (node (ref "U1") (pin "20") (pinfunction "A1_20") (pintype "passive"))
    )
    (net (code "115") (name "unconnected-(U1-A2-Pad21)") (class "Default")
      (node (ref "U1") (pin "21") (pinfunction "A2_21") (pintype "passive"))
    )
    (net (code "116") (name "unconnected-(U1-A3-Pad22)") (class "Default")
      (node (ref "U1") (pin "22") (pinfunction "A3_22") (pintype "passive"))
    )
    (net (code "117") (name "unconnected-(U1-A6-Pad25)") (class "Default")
      (node (ref "U1") (pin "25") (pinfunction "A6_25") (pintype "passive"))
    )
    (net (code "118") (name "unconnected-(U1-A7-Pad26)") (class "Default")
      (node (ref "U1") (pin "26") (pinfunction "A7_26") (pintype "passive"))
    )
    (net (code "119") (name "unconnected-(U1-D8-Pad11)") (class "Default")
      (node (ref "U1") (pin "11") (pinfunction "D8_11") (pintype "passive"))
    )
    (net (code "120") (name "unconnected-(U1-REF-Pad18)") (class "Default")
      (node (ref "U1") (pin "18") (pinfunction "REF_18") (pintype "passive"))
    )
    (net (code "121") (name "unconnected-(U1-RST-Pad3)") (class "Default")
      (node (ref "U1") (pin "3") (pinfunction "RST_3") (pintype "passive"))
    )
    (net (code "122") (name "unconnected-(U1-RST-Pad28)") (class "Default")
      (node (ref "U1") (pin "28") (pinfunction "RST_28") (pintype "passive"))
    )
    (net (code "123") (name "unconnected-(U1-RXD-Pad2)") (class "Default")
      (node (ref "U1") (pin "2") (pinfunction "RXD_2") (pintype "passive"))
    )
    (net (code "124") (name "unconnected-(U1-TXD-Pad1)") (class "Default")
      (node (ref "U1") (pin "1") (pinfunction "TXD_1") (pintype "passive"))
    )
    (net (code "125") (name "unconnected-(U2-GND-Pad4)") (class "Default")
      (node (ref "U2") (pin "4") (pinfunction "GND_4") (pintype "passive"))
    )
    (net (code "126") (name "unconnected-(U3-OUT--Pad3)") (class "Default")
      (node (ref "U3") (pin "3") (pinfunction "OUT-_3") (pintype "passive"))
    )
    (net (code "127") (name "unconnected-(U4-EN-Pad6)") (class "Default")
      (node (ref "U4") (pin "6") (pinfunction "EN_6") (pintype "passive"))
    )
    (net (code "128") (name "unconnected-(U4-Vcc3-Pad1)") (class "Default")
      (node (ref "U4") (pin "1") (pinfunction "Vcc3_1") (pintype "passive"))
    )
    (net (code "129") (name "unconnected-(U5-EEP-Pad12)") (class "Default")
      (node (ref "U5") (pin "12") (pinfunction "EEP_12") (pintype "passive"))
    )
    (net (code "130") (name "unconnected-(U5-ULT-Pad7)") (class "Default")
      (node (ref "U5") (pin "7") (pinfunction "ULT_7") (pintype "passive"))
    )
  )
)
